# design.net
KiCad netlist of a schematic drawn in Altium Designer
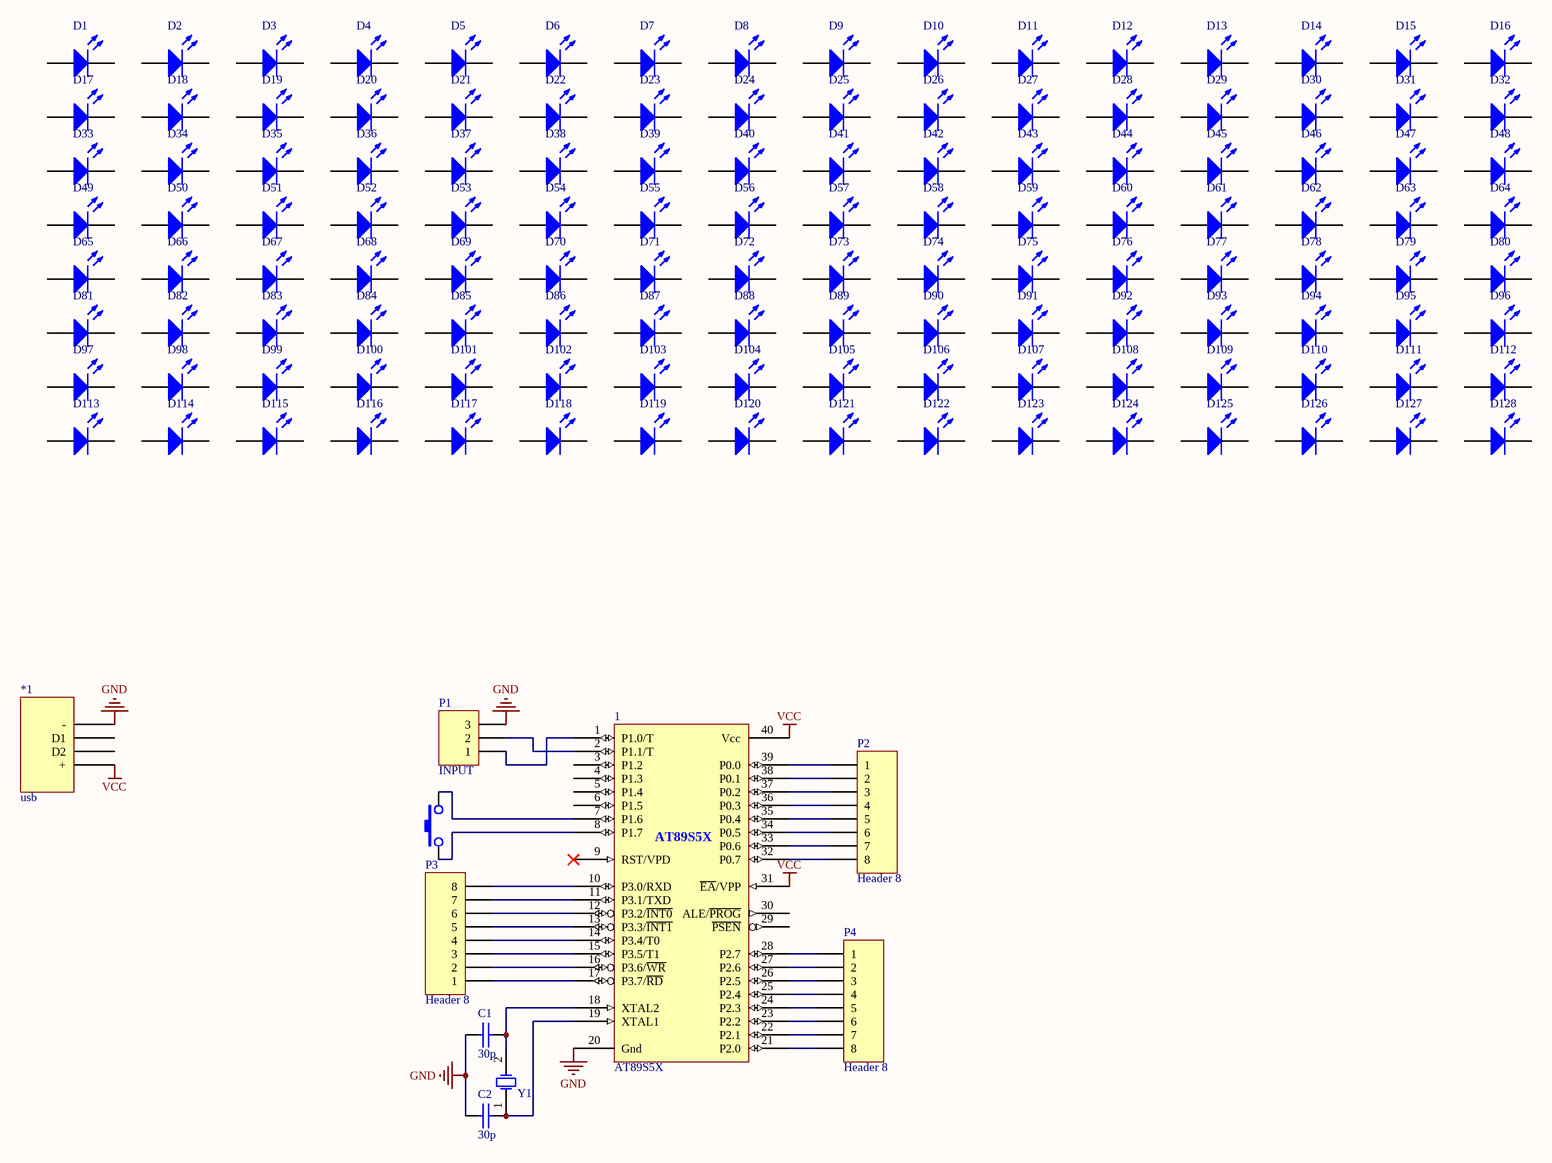
[diagram p0: 单片机频谱显示.SchDoc]

(export (version "E")
  (design (tool "Eeschema 10.0.6"))
  (components
    (comp (ref "*1") (value "usb") (footprint "USB") (libsource (lib "插件") (part "usb")))
    (comp (ref "1") (value "AT89S5X") (footprint "DIP-40") (libsource (lib "单片机及相关") (part "AT89S5X")))
    (comp (ref "C1")
      (value "30p")
      (footprint "RAD0.2")
      (fields (field (name "Comment") "CAP"))
      (libsource (lib "常用元件库") (part "CAP"))
    )
    (comp (ref "C2")
      (value "30p")
      (footprint "RAD0.2")
      (fields (field (name "Comment") "CAP"))
      (libsource (lib "常用元件库") (part "CAP"))
    )
    (comp (ref "D1")
      (value "LED0")
      (footprint "LED")
      (description "Typical INFRARED GaAs LED")
      (fields (field (name "PUBLISHER") "Altium Limited"))
      (libsource (lib "常用元件库") (part "LED0"))
    )
    (comp (ref "D2")
      (value "LED0")
      (footprint "LED")
      (description "Typical INFRARED GaAs LED")
      (fields (field (name "PUBLISHER") "Altium Limited"))
      (libsource (lib "常用元件库") (part "LED0"))
    )
    (comp (ref "D3")
      (value "LED0")
      (footprint "LED")
      (description "Typical INFRARED GaAs LED")
      (fields (field (name "PUBLISHER") "Altium Limited"))
      (libsource (lib "常用元件库") (part "LED0"))
    )
    (comp (ref "D4")
      (value "LED0")
      (footprint "LED")
      (description "Typical INFRARED GaAs LED")
      (fields (field (name "PUBLISHER") "Altium Limited"))
      (libsource (lib "常用元件库") (part "LED0"))
    )
    (comp (ref "D5")
      (value "LED0")
      (footprint "LED")
      (description "Typical INFRARED GaAs LED")
      (fields (field (name "PUBLISHER") "Altium Limited"))
      (libsource (lib "常用元件库") (part "LED0"))
    )
    (comp (ref "D6")
      (value "LED0")
      (footprint "LED")
      (description "Typical INFRARED GaAs LED")
      (fields (field (name "PUBLISHER") "Altium Limited"))
      (libsource (lib "常用元件库") (part "LED0"))
    )
    (comp (ref "D7")
      (value "LED0")
      (footprint "LED")
      (description "Typical INFRARED GaAs LED")
      (fields (field (name "PUBLISHER") "Altium Limited"))
      (libsource (lib "常用元件库") (part "LED0"))
    )
    (comp (ref "D8")
      (value "LED0")
      (footprint "LED")
      (description "Typical INFRARED GaAs LED")
      (fields (field (name "PUBLISHER") "Altium Limited"))
      (libsource (lib "常用元件库") (part "LED0"))
    )
    (comp (ref "D9")
      (value "LED0")
      (footprint "LED")
      (description "Typical INFRARED GaAs LED")
      (fields (field (name "PUBLISHER") "Altium Limited"))
      (libsource (lib "常用元件库") (part "LED0"))
    )
    (comp (ref "D10")
      (value "LED0")
      (footprint "LED")
      (description "Typical INFRARED GaAs LED")
      (fields (field (name "PUBLISHER") "Altium Limited"))
      (libsource (lib "常用元件库") (part "LED0"))
    )
    (comp (ref "D11")
      (value "LED0")
      (footprint "LED")
      (description "Typical INFRARED GaAs LED")
      (fields (field (name "PUBLISHER") "Altium Limited"))
      (libsource (lib "常用元件库") (part "LED0"))
    )
    (comp (ref "D12")
      (value "LED0")
      (footprint "LED")
      (description "Typical INFRARED GaAs LED")
      (fields (field (name "PUBLISHER") "Altium Limited"))
      (libsource (lib "常用元件库") (part "LED0"))
    )
    (comp (ref "D13")
      (value "LED0")
      (footprint "LED")
      (description "Typical INFRARED GaAs LED")
      (fields (field (name "PUBLISHER") "Altium Limited"))
      (libsource (lib "常用元件库") (part "LED0"))
    )
    (comp (ref "D14")
      (value "LED0")
      (footprint "LED")
      (description "Typical INFRARED GaAs LED")
      (fields (field (name "PUBLISHER") "Altium Limited"))
      (libsource (lib "常用元件库") (part "LED0"))
    )
    (comp (ref "D15")
      (value "LED0")
      (footprint "LED")
      (description "Typical INFRARED GaAs LED")
      (fields (field (name "PUBLISHER") "Altium Limited"))
      (libsource (lib "常用元件库") (part "LED0"))
    )
    (comp (ref "D16")
      (value "LED0")
      (footprint "LED")
      (description "Typical INFRARED GaAs LED")
      (fields (field (name "PUBLISHER") "Altium Limited"))
      (libsource (lib "常用元件库") (part "LED0"))
    )
    (comp (ref "D17")
      (value "LED0")
      (footprint "LED")
      (description "Typical INFRARED GaAs LED")
      (fields (field (name "PUBLISHER") "Altium Limited"))
      (libsource (lib "常用元件库") (part "LED0"))
    )
    (comp (ref "D18")
      (value "LED0")
      (footprint "LED")
      (description "Typical INFRARED GaAs LED")
      (fields (field (name "PUBLISHER") "Altium Limited"))
      (libsource (lib "常用元件库") (part "LED0"))
    )
    (comp (ref "D19")
      (value "LED0")
      (footprint "LED")
      (description "Typical INFRARED GaAs LED")
      (fields (field (name "PUBLISHER") "Altium Limited"))
      (libsource (lib "常用元件库") (part "LED0"))
    )
    (comp (ref "D20")
      (value "LED0")
      (footprint "LED")
      (description "Typical INFRARED GaAs LED")
      (fields (field (name "PUBLISHER") "Altium Limited"))
      (libsource (lib "常用元件库") (part "LED0"))
    )
    (comp (ref "D21")
      (value "LED0")
      (footprint "LED")
      (description "Typical INFRARED GaAs LED")
      (fields (field (name "PUBLISHER") "Altium Limited"))
      (libsource (lib "常用元件库") (part "LED0"))
    )
    (comp (ref "D22")
      (value "LED0")
      (footprint "LED")
      (description "Typical INFRARED GaAs LED")
      (fields (field (name "PUBLISHER") "Altium Limited"))
      (libsource (lib "常用元件库") (part "LED0"))
    )
    (comp (ref "D23")
      (value "LED0")
      (footprint "LED")
      (description "Typical INFRARED GaAs LED")
      (fields (field (name "PUBLISHER") "Altium Limited"))
      (libsource (lib "常用元件库") (part "LED0"))
    )
    (comp (ref "D24")
      (value "LED0")
      (footprint "LED")
      (description "Typical INFRARED GaAs LED")
      (fields (field (name "PUBLISHER") "Altium Limited"))
      (libsource (lib "常用元件库") (part "LED0"))
    )
    (comp (ref "D25")
      (value "LED0")
      (footprint "LED")
      (description "Typical INFRARED GaAs LED")
      (fields (field (name "PUBLISHER") "Altium Limited"))
      (libsource (lib "常用元件库") (part "LED0"))
    )
    (comp (ref "D26")
      (value "LED0")
      (footprint "LED")
      (description "Typical INFRARED GaAs LED")
      (fields (field (name "PUBLISHER") "Altium Limited"))
      (libsource (lib "常用元件库") (part "LED0"))
    )
    (comp (ref "D27")
      (value "LED0")
      (footprint "LED")
      (description "Typical INFRARED GaAs LED")
      (fields (field (name "PUBLISHER") "Altium Limited"))
      (libsource (lib "常用元件库") (part "LED0"))
    )
    (comp (ref "D28")
      (value "LED0")
      (footprint "LED")
      (description "Typical INFRARED GaAs LED")
      (fields (field (name "PUBLISHER") "Altium Limited"))
      (libsource (lib "常用元件库") (part "LED0"))
    )
    (comp (ref "D29")
      (value "LED0")
      (footprint "LED")
      (description "Typical INFRARED GaAs LED")
      (fields (field (name "PUBLISHER") "Altium Limited"))
      (libsource (lib "常用元件库") (part "LED0"))
    )
    (comp (ref "D30")
      (value "LED0")
      (footprint "LED")
      (description "Typical INFRARED GaAs LED")
      (fields (field (name "PUBLISHER") "Altium Limited"))
      (libsource (lib "常用元件库") (part "LED0"))
    )
    (comp (ref "D31")
      (value "LED0")
      (footprint "LED")
      (description "Typical INFRARED GaAs LED")
      (fields (field (name "PUBLISHER") "Altium Limited"))
      (libsource (lib "常用元件库") (part "LED0"))
    )
    (comp (ref "D32")
      (value "LED0")
      (footprint "LED")
      (description "Typical INFRARED GaAs LED")
      (fields (field (name "PUBLISHER") "Altium Limited"))
      (libsource (lib "常用元件库") (part "LED0"))
    )
    (comp (ref "D33")
      (value "LED0")
      (footprint "LED")
      (description "Typical INFRARED GaAs LED")
      (fields (field (name "PUBLISHER") "Altium Limited"))
      (libsource (lib "常用元件库") (part "LED0"))
    )
    (comp (ref "D34")
      (value "LED0")
      (footprint "LED")
      (description "Typical INFRARED GaAs LED")
      (fields (field (name "PUBLISHER") "Altium Limited"))
      (libsource (lib "常用元件库") (part "LED0"))
    )
    (comp (ref "D35")
      (value "LED0")
      (footprint "LED")
      (description "Typical INFRARED GaAs LED")
      (fields (field (name "PUBLISHER") "Altium Limited"))
      (libsource (lib "常用元件库") (part "LED0"))
    )
    (comp (ref "D36")
      (value "LED0")
      (footprint "LED")
      (description "Typical INFRARED GaAs LED")
      (fields (field (name "PUBLISHER") "Altium Limited"))
      (libsource (lib "常用元件库") (part "LED0"))
    )
    (comp (ref "D37")
      (value "LED0")
      (footprint "LED")
      (description "Typical INFRARED GaAs LED")
      (fields (field (name "PUBLISHER") "Altium Limited"))
      (libsource (lib "常用元件库") (part "LED0"))
    )
    (comp (ref "D38")
      (value "LED0")
      (footprint "LED")
      (description "Typical INFRARED GaAs LED")
      (fields (field (name "PUBLISHER") "Altium Limited"))
      (libsource (lib "常用元件库") (part "LED0"))
    )
    (comp (ref "D39")
      (value "LED0")
      (footprint "LED")
      (description "Typical INFRARED GaAs LED")
      (fields (field (name "PUBLISHER") "Altium Limited"))
      (libsource (lib "常用元件库") (part "LED0"))
    )
    (comp (ref "D40")
      (value "LED0")
      (footprint "LED")
      (description "Typical INFRARED GaAs LED")
      (fields (field (name "PUBLISHER") "Altium Limited"))
      (libsource (lib "常用元件库") (part "LED0"))
    )
    (comp (ref "D41")
      (value "LED0")
      (footprint "LED")
      (description "Typical INFRARED GaAs LED")
      (fields (field (name "PUBLISHER") "Altium Limited"))
      (libsource (lib "常用元件库") (part "LED0"))
    )
    (comp (ref "D42")
      (value "LED0")
      (footprint "LED")
      (description "Typical INFRARED GaAs LED")
      (fields (field (name "PUBLISHER") "Altium Limited"))
      (libsource (lib "常用元件库") (part "LED0"))
    )
    (comp (ref "D43")
      (value "LED0")
      (footprint "LED")
      (description "Typical INFRARED GaAs LED")
      (fields (field (name "PUBLISHER") "Altium Limited"))
      (libsource (lib "常用元件库") (part "LED0"))
    )
    (comp (ref "D44")
      (value "LED0")
      (footprint "LED")
      (description "Typical INFRARED GaAs LED")
      (fields (field (name "PUBLISHER") "Altium Limited"))
      (libsource (lib "常用元件库") (part "LED0"))
    )
    (comp (ref "D45")
      (value "LED0")
      (footprint "LED")
      (description "Typical INFRARED GaAs LED")
      (fields (field (name "PUBLISHER") "Altium Limited"))
      (libsource (lib "常用元件库") (part "LED0"))
    )
    (comp (ref "D46")
      (value "LED0")
      (footprint "LED")
      (description "Typical INFRARED GaAs LED")
      (fields (field (name "PUBLISHER") "Altium Limited"))
      (libsource (lib "常用元件库") (part "LED0"))
    )
    (comp (ref "D47")
      (value "LED0")
      (footprint "LED")
      (description "Typical INFRARED GaAs LED")
      (fields (field (name "PUBLISHER") "Altium Limited"))
      (libsource (lib "常用元件库") (part "LED0"))
    )
    (comp (ref "D48")
      (value "LED0")
      (footprint "LED")
      (description "Typical INFRARED GaAs LED")
      (fields (field (name "PUBLISHER") "Altium Limited"))
      (libsource (lib "常用元件库") (part "LED0"))
    )
    (comp (ref "D49")
      (value "LED0")
      (footprint "LED")
      (description "Typical INFRARED GaAs LED")
      (fields (field (name "PUBLISHER") "Altium Limited"))
      (libsource (lib "常用元件库") (part "LED0"))
    )
    (comp (ref "D50")
      (value "LED0")
      (footprint "LED")
      (description "Typical INFRARED GaAs LED")
      (fields (field (name "PUBLISHER") "Altium Limited"))
      (libsource (lib "常用元件库") (part "LED0"))
    )
    (comp (ref "D51")
      (value "LED0")
      (footprint "LED")
      (description "Typical INFRARED GaAs LED")
      (fields (field (name "PUBLISHER") "Altium Limited"))
      (libsource (lib "常用元件库") (part "LED0"))
    )
    (comp (ref "D52")
      (value "LED0")
      (footprint "LED")
      (description "Typical INFRARED GaAs LED")
      (fields (field (name "PUBLISHER") "Altium Limited"))
      (libsource (lib "常用元件库") (part "LED0"))
    )
    (comp (ref "D53")
      (value "LED0")
      (footprint "LED")
      (description "Typical INFRARED GaAs LED")
      (fields (field (name "PUBLISHER") "Altium Limited"))
      (libsource (lib "常用元件库") (part "LED0"))
    )
    (comp (ref "D54")
      (value "LED0")
      (footprint "LED")
      (description "Typical INFRARED GaAs LED")
      (fields (field (name "PUBLISHER") "Altium Limited"))
      (libsource (lib "常用元件库") (part "LED0"))
    )
    (comp (ref "D55")
      (value "LED0")
      (footprint "LED")
      (description "Typical INFRARED GaAs LED")
      (fields (field (name "PUBLISHER") "Altium Limited"))
      (libsource (lib "常用元件库") (part "LED0"))
    )
    (comp (ref "D56")
      (value "LED0")
      (footprint "LED")
      (description "Typical INFRARED GaAs LED")
      (fields (field (name "PUBLISHER") "Altium Limited"))
      (libsource (lib "常用元件库") (part "LED0"))
    )
    (comp (ref "D57")
      (value "LED0")
      (footprint "LED")
      (description "Typical INFRARED GaAs LED")
      (fields (field (name "PUBLISHER") "Altium Limited"))
      (libsource (lib "常用元件库") (part "LED0"))
    )
    (comp (ref "D58")
      (value "LED0")
      (footprint "LED")
      (description "Typical INFRARED GaAs LED")
      (fields (field (name "PUBLISHER") "Altium Limited"))
      (libsource (lib "常用元件库") (part "LED0"))
    )
    (comp (ref "D59")
      (value "LED0")
      (footprint "LED")
      (description "Typical INFRARED GaAs LED")
      (fields (field (name "PUBLISHER") "Altium Limited"))
      (libsource (lib "常用元件库") (part "LED0"))
    )
    (comp (ref "D60")
      (value "LED0")
      (footprint "LED")
      (description "Typical INFRARED GaAs LED")
      (fields (field (name "PUBLISHER") "Altium Limited"))
      (libsource (lib "常用元件库") (part "LED0"))
    )
    (comp (ref "D61")
      (value "LED0")
      (footprint "LED")
      (description "Typical INFRARED GaAs LED")
      (fields (field (name "PUBLISHER") "Altium Limited"))
      (libsource (lib "常用元件库") (part "LED0"))
    )
    (comp (ref "D62")
      (value "LED0")
      (footprint "LED")
      (description "Typical INFRARED GaAs LED")
      (fields (field (name "PUBLISHER") "Altium Limited"))
      (libsource (lib "常用元件库") (part "LED0"))
    )
    (comp (ref "D63")
      (value "LED0")
      (footprint "LED")
      (description "Typical INFRARED GaAs LED")
      (fields (field (name "PUBLISHER") "Altium Limited"))
      (libsource (lib "常用元件库") (part "LED0"))
    )
    (comp (ref "D64")
      (value "LED0")
      (footprint "LED")
      (description "Typical INFRARED GaAs LED")
      (fields (field (name "PUBLISHER") "Altium Limited"))
      (libsource (lib "常用元件库") (part "LED0"))
    )
    (comp (ref "D65")
      (value "LED0")
      (footprint "LED")
      (description "Typical INFRARED GaAs LED")
      (fields (field (name "PUBLISHER") "Altium Limited"))
      (libsource (lib "常用元件库") (part "LED0"))
    )
    (comp (ref "D66")
      (value "LED0")
      (footprint "LED")
      (description "Typical INFRARED GaAs LED")
      (fields (field (name "PUBLISHER") "Altium Limited"))
      (libsource (lib "常用元件库") (part "LED0"))
    )
    (comp (ref "D67")
      (value "LED0")
      (footprint "LED")
      (description "Typical INFRARED GaAs LED")
      (fields (field (name "PUBLISHER") "Altium Limited"))
      (libsource (lib "常用元件库") (part "LED0"))
    )
    (comp (ref "D68")
      (value "LED0")
      (footprint "LED")
      (description "Typical INFRARED GaAs LED")
      (fields (field (name "PUBLISHER") "Altium Limited"))
      (libsource (lib "常用元件库") (part "LED0"))
    )
    (comp (ref "D69")
      (value "LED0")
      (footprint "LED")
      (description "Typical INFRARED GaAs LED")
      (fields (field (name "PUBLISHER") "Altium Limited"))
      (libsource (lib "常用元件库") (part "LED0"))
    )
    (comp (ref "D70")
      (value "LED0")
      (footprint "LED")
      (description "Typical INFRARED GaAs LED")
      (fields (field (name "PUBLISHER") "Altium Limited"))
      (libsource (lib "常用元件库") (part "LED0"))
    )
    (comp (ref "D71")
      (value "LED0")
      (footprint "LED")
      (description "Typical INFRARED GaAs LED")
      (fields (field (name "PUBLISHER") "Altium Limited"))
      (libsource (lib "常用元件库") (part "LED0"))
    )
    (comp (ref "D72")
      (value "LED0")
      (footprint "LED")
      (description "Typical INFRARED GaAs LED")
      (fields (field (name "PUBLISHER") "Altium Limited"))
      (libsource (lib "常用元件库") (part "LED0"))
    )
    (comp (ref "D73")
      (value "LED0")
      (footprint "LED")
      (description "Typical INFRARED GaAs LED")
      (fields (field (name "PUBLISHER") "Altium Limited"))
      (libsource (lib "常用元件库") (part "LED0"))
    )
    (comp (ref "D74")
      (value "LED0")
      (footprint "LED")
      (description "Typical INFRARED GaAs LED")
      (fields (field (name "PUBLISHER") "Altium Limited"))
      (libsource (lib "常用元件库") (part "LED0"))
    )
    (comp (ref "D75")
      (value "LED0")
      (footprint "LED")
      (description "Typical INFRARED GaAs LED")
      (fields (field (name "PUBLISHER") "Altium Limited"))
      (libsource (lib "常用元件库") (part "LED0"))
    )
    (comp (ref "D76")
      (value "LED0")
      (footprint "LED")
      (description "Typical INFRARED GaAs LED")
      (fields (field (name "PUBLISHER") "Altium Limited"))
      (libsource (lib "常用元件库") (part "LED0"))
    )
    (comp (ref "D77")
      (value "LED0")
      (footprint "LED")
      (description "Typical INFRARED GaAs LED")
      (fields (field (name "PUBLISHER") "Altium Limited"))
      (libsource (lib "常用元件库") (part "LED0"))
    )
    (comp (ref "D78")
      (value "LED0")
      (footprint "LED")
      (description "Typical INFRARED GaAs LED")
      (fields (field (name "PUBLISHER") "Altium Limited"))
      (libsource (lib "常用元件库") (part "LED0"))
    )
    (comp (ref "D79")
      (value "LED0")
      (footprint "LED")
      (description "Typical INFRARED GaAs LED")
      (fields (field (name "PUBLISHER") "Altium Limited"))
      (libsource (lib "常用元件库") (part "LED0"))
    )
    (comp (ref "D80")
      (value "LED0")
      (footprint "LED")
      (description "Typical INFRARED GaAs LED")
      (fields (field (name "PUBLISHER") "Altium Limited"))
      (libsource (lib "常用元件库") (part "LED0"))
    )
    (comp (ref "D81")
      (value "LED0")
      (footprint "LED")
      (description "Typical INFRARED GaAs LED")
      (fields (field (name "PUBLISHER") "Altium Limited"))
      (libsource (lib "常用元件库") (part "LED0"))
    )
    (comp (ref "D82")
      (value "LED0")
      (footprint "LED")
      (description "Typical INFRARED GaAs LED")
      (fields (field (name "PUBLISHER") "Altium Limited"))
      (libsource (lib "常用元件库") (part "LED0"))
    )
    (comp (ref "D83")
      (value "LED0")
      (footprint "LED")
      (description "Typical INFRARED GaAs LED")
      (fields (field (name "PUBLISHER") "Altium Limited"))
      (libsource (lib "常用元件库") (part "LED0"))
    )
    (comp (ref "D84")
      (value "LED0")
      (footprint "LED")
      (description "Typical INFRARED GaAs LED")
      (fields (field (name "PUBLISHER") "Altium Limited"))
      (libsource (lib "常用元件库") (part "LED0"))
    )
    (comp (ref "D85")
      (value "LED0")
      (footprint "LED")
      (description "Typical INFRARED GaAs LED")
      (fields (field (name "PUBLISHER") "Altium Limited"))
      (libsource (lib "常用元件库") (part "LED0"))
    )
    (comp (ref "D86")
      (value "LED0")
      (footprint "LED")
      (description "Typical INFRARED GaAs LED")
      (fields (field (name "PUBLISHER") "Altium Limited"))
      (libsource (lib "常用元件库") (part "LED0"))
    )
    (comp (ref "D87")
      (value "LED0")
      (footprint "LED")
      (description "Typical INFRARED GaAs LED")
      (fields (field (name "PUBLISHER") "Altium Limited"))
      (libsource (lib "常用元件库") (part "LED0"))
    )
    (comp (ref "D88")
      (value "LED0")
      (footprint "LED")
      (description "Typical INFRARED GaAs LED")
      (fields (field (name "PUBLISHER") "Altium Limited"))
      (libsource (lib "常用元件库") (part "LED0"))
    )
    (comp (ref "D89")
      (value "LED0")
      (footprint "LED")
      (description "Typical INFRARED GaAs LED")
      (fields (field (name "PUBLISHER") "Altium Limited"))
      (libsource (lib "常用元件库") (part "LED0"))
    )
    (comp (ref "D90")
      (value "LED0")
      (footprint "LED")
      (description "Typical INFRARED GaAs LED")
      (fields (field (name "PUBLISHER") "Altium Limited"))
      (libsource (lib "常用元件库") (part "LED0"))
    )
    (comp (ref "D91")
      (value "LED0")
      (footprint "LED")
      (description "Typical INFRARED GaAs LED")
      (fields (field (name "PUBLISHER") "Altium Limited"))
      (libsource (lib "常用元件库") (part "LED0"))
    )
    (comp (ref "D92")
      (value "LED0")
      (footprint "LED")
      (description "Typical INFRARED GaAs LED")
      (fields (field (name "PUBLISHER") "Altium Limited"))
      (libsource (lib "常用元件库") (part "LED0"))
    )
    (comp (ref "D93")
      (value "LED0")
      (footprint "LED")
      (description "Typical INFRARED GaAs LED")
      (fields (field (name "PUBLISHER") "Altium Limited"))
      (libsource (lib "常用元件库") (part "LED0"))
    )
    (comp (ref "D94")
      (value "LED0")
      (footprint "LED")
      (description "Typical INFRARED GaAs LED")
      (fields (field (name "PUBLISHER") "Altium Limited"))
      (libsource (lib "常用元件库") (part "LED0"))
    )
    (comp (ref "D95")
      (value "LED0")
      (footprint "LED")
      (description "Typical INFRARED GaAs LED")
      (fields (field (name "PUBLISHER") "Altium Limited"))
      (libsource (lib "常用元件库") (part "LED0"))
    )
    (comp (ref "D96")
      (value "LED0")
      (footprint "LED")
      (description "Typical INFRARED GaAs LED")
      (fields (field (name "PUBLISHER") "Altium Limited"))
      (libsource (lib "常用元件库") (part "LED0"))
    )
    (comp (ref "D97")
      (value "LED0")
      (footprint "LED")
      (description "Typical INFRARED GaAs LED")
      (fields (field (name "PUBLISHER") "Altium Limited"))
      (libsource (lib "常用元件库") (part "LED0"))
    )
    (comp (ref "D98")
      (value "LED0")
      (footprint "LED")
      (description "Typical INFRARED GaAs LED")
      (fields (field (name "PUBLISHER") "Altium Limited"))
      (libsource (lib "常用元件库") (part "LED0"))
    )
    (comp (ref "D99")
      (value "LED0")
      (footprint "LED")
      (description "Typical INFRARED GaAs LED")
      (fields (field (name "PUBLISHER") "Altium Limited"))
      (libsource (lib "常用元件库") (part "LED0"))
    )
    (comp (ref "D100")
      (value "LED0")
      (footprint "LED")
      (description "Typical INFRARED GaAs LED")
      (fields (field (name "PUBLISHER") "Altium Limited"))
      (libsource (lib "常用元件库") (part "LED0"))
    )
    (comp (ref "D101")
      (value "LED0")
      (footprint "LED")
      (description "Typical INFRARED GaAs LED")
      (fields (field (name "PUBLISHER") "Altium Limited"))
      (libsource (lib "常用元件库") (part "LED0"))
    )
    (comp (ref "D102")
      (value "LED0")
      (footprint "LED")
      (description "Typical INFRARED GaAs LED")
      (fields (field (name "PUBLISHER") "Altium Limited"))
      (libsource (lib "常用元件库") (part "LED0"))
    )
    (comp (ref "D103")
      (value "LED0")
      (footprint "LED")
      (description "Typical INFRARED GaAs LED")
      (fields (field (name "PUBLISHER") "Altium Limited"))
      (libsource (lib "常用元件库") (part "LED0"))
    )
    (comp (ref "D104")
      (value "LED0")
      (footprint "LED")
      (description "Typical INFRARED GaAs LED")
      (fields (field (name "PUBLISHER") "Altium Limited"))
      (libsource (lib "常用元件库") (part "LED0"))
    )
    (comp (ref "D105")
      (value "LED0")
      (footprint "LED")
      (description "Typical INFRARED GaAs LED")
      (fields (field (name "PUBLISHER") "Altium Limited"))
      (libsource (lib "常用元件库") (part "LED0"))
    )
    (comp (ref "D106")
      (value "LED0")
      (footprint "LED")
      (description "Typical INFRARED GaAs LED")
      (fields (field (name "PUBLISHER") "Altium Limited"))
      (libsource (lib "常用元件库") (part "LED0"))
    )
    (comp (ref "D107")
      (value "LED0")
      (footprint "LED")
      (description "Typical INFRARED GaAs LED")
      (fields (field (name "PUBLISHER") "Altium Limited"))
      (libsource (lib "常用元件库") (part "LED0"))
    )
    (comp (ref "D108")
      (value "LED0")
      (footprint "LED")
      (description "Typical INFRARED GaAs LED")
      (fields (field (name "PUBLISHER") "Altium Limited"))
      (libsource (lib "常用元件库") (part "LED0"))
    )
    (comp (ref "D109")
      (value "LED0")
      (footprint "LED")
      (description "Typical INFRARED GaAs LED")
      (fields (field (name "PUBLISHER") "Altium Limited"))
      (libsource (lib "常用元件库") (part "LED0"))
    )
    (comp (ref "D110")
      (value "LED0")
      (footprint "LED")
      (description "Typical INFRARED GaAs LED")
      (fields (field (name "PUBLISHER") "Altium Limited"))
      (libsource (lib "常用元件库") (part "LED0"))
    )
    (comp (ref "D111")
      (value "LED0")
      (footprint "LED")
      (description "Typical INFRARED GaAs LED")
      (fields (field (name "PUBLISHER") "Altium Limited"))
      (libsource (lib "常用元件库") (part "LED0"))
    )
    (comp (ref "D112")
      (value "LED0")
      (footprint "LED")
      (description "Typical INFRARED GaAs LED")
      (fields (field (name "PUBLISHER") "Altium Limited"))
      (libsource (lib "常用元件库") (part "LED0"))
    )
    (comp (ref "D113")
      (value "LED0")
      (footprint "LED")
      (description "Typical INFRARED GaAs LED")
      (fields (field (name "PUBLISHER") "Altium Limited"))
      (libsource (lib "常用元件库") (part "LED0"))
    )
    (comp (ref "D114")
      (value "LED0")
      (footprint "LED")
      (description "Typical INFRARED GaAs LED")
      (fields (field (name "PUBLISHER") "Altium Limited"))
      (libsource (lib "常用元件库") (part "LED0"))
    )
    (comp (ref "D115")
      (value "LED0")
      (footprint "LED")
      (description "Typical INFRARED GaAs LED")
      (fields (field (name "PUBLISHER") "Altium Limited"))
      (libsource (lib "常用元件库") (part "LED0"))
    )
    (comp (ref "D116")
      (value "LED0")
      (footprint "LED")
      (description "Typical INFRARED GaAs LED")
      (fields (field (name "PUBLISHER") "Altium Limited"))
      (libsource (lib "常用元件库") (part "LED0"))
    )
    (comp (ref "D117")
      (value "LED0")
      (footprint "LED")
      (description "Typical INFRARED GaAs LED")
      (fields (field (name "PUBLISHER") "Altium Limited"))
      (libsource (lib "常用元件库") (part "LED0"))
    )
    (comp (ref "D118")
      (value "LED0")
      (footprint "LED")
      (description "Typical INFRARED GaAs LED")
      (fields (field (name "PUBLISHER") "Altium Limited"))
      (libsource (lib "常用元件库") (part "LED0"))
    )
    (comp (ref "D119")
      (value "LED0")
      (footprint "LED")
      (description "Typical INFRARED GaAs LED")
      (fields (field (name "PUBLISHER") "Altium Limited"))
      (libsource (lib "常用元件库") (part "LED0"))
    )
    (comp (ref "D120")
      (value "LED0")
      (footprint "LED")
      (description "Typical INFRARED GaAs LED")
      (fields (field (name "PUBLISHER") "Altium Limited"))
      (libsource (lib "常用元件库") (part "LED0"))
    )
    (comp (ref "D121")
      (value "LED0")
      (footprint "LED")
      (description "Typical INFRARED GaAs LED")
      (fields (field (name "PUBLISHER") "Altium Limited"))
      (libsource (lib "常用元件库") (part "LED0"))
    )
    (comp (ref "D122")
      (value "LED0")
      (footprint "LED")
      (description "Typical INFRARED GaAs LED")
      (fields (field (name "PUBLISHER") "Altium Limited"))
      (libsource (lib "常用元件库") (part "LED0"))
    )
    (comp (ref "D123")
      (value "LED0")
      (footprint "LED")
      (description "Typical INFRARED GaAs LED")
      (fields (field (name "PUBLISHER") "Altium Limited"))
      (libsource (lib "常用元件库") (part "LED0"))
    )
    (comp (ref "D124")
      (value "LED0")
      (footprint "LED")
      (description "Typical INFRARED GaAs LED")
      (fields (field (name "PUBLISHER") "Altium Limited"))
      (libsource (lib "常用元件库") (part "LED0"))
    )
    (comp (ref "D125")
      (value "LED0")
      (footprint "LED")
      (description "Typical INFRARED GaAs LED")
      (fields (field (name "PUBLISHER") "Altium Limited"))
      (libsource (lib "常用元件库") (part "LED0"))
    )
    (comp (ref "D126")
      (value "LED0")
      (footprint "LED")
      (description "Typical INFRARED GaAs LED")
      (fields (field (name "PUBLISHER") "Altium Limited"))
      (libsource (lib "常用元件库") (part "LED0"))
    )
    (comp (ref "D127")
      (value "LED0")
      (footprint "LED")
      (description "Typical INFRARED GaAs LED")
      (fields (field (name "PUBLISHER") "Altium Limited"))
      (libsource (lib "常用元件库") (part "LED0"))
    )
    (comp (ref "D128")
      (value "LED0")
      (footprint "LED")
      (description "Typical INFRARED GaAs LED")
      (fields (field (name "PUBLISHER") "Altium Limited"))
      (libsource (lib "常用元件库") (part "LED0"))
    )
    (comp (ref "key1") (value "KEY") (footprint "KeyA") (libsource (lib "常用元件库") (part "KEY")))
    (comp (ref "P1")
      (value "INPUT")
      (footprint "HDR1X3")
      (description "Header, 3-Pin")
      (fields (field (name "PUBLISHER") "Altium Limited"))
      (libsource (lib "常用元件库") (part "Header 3"))
    )
    (comp (ref "P2")
      (value "Header 8")
      (footprint "HDR1X8")
      (description "Header, 8-Pin")
      (fields (field (name "PUBLISHER") "Altium Limited"))
      (libsource (lib "") (part "Header 8_1"))
    )
    (comp (ref "P3")
      (value "Header 8")
      (footprint "HDR1X8")
      (description "Header, 8-Pin")
      (fields (field (name "PUBLISHER") "Altium Limited"))
      (libsource (lib "常用元件库") (part "Header 8"))
    )
    (comp (ref "P4")
      (value "Header 8")
      (footprint "HDR1X8")
      (description "Header, 8-Pin")
      (fields (field (name "PUBLISHER") "Altium Limited"))
      (libsource (lib "") (part "Header 8_1"))
    )
    (comp (ref "Y1")
      (value "XTAL")
      (footprint "XTAL")
      (description "Crystal Oscillator")
      (fields (field (name "PUBLISHER") "Altium Limited"))
      (libsource (lib "常用元件库") (part "XTAL"))
    )
  )
  (nets
    (net (code "1") (name "GND") (class "Default")
      (node (ref "*1") (pin "-") (pinfunction "-_-") (pintype "power_in"))
      (node (ref "1") (pin "20") (pinfunction "Gnd_20") (pintype "power_in"))
      (node (ref "C1") (pin "1") (pinfunction "1_1") (pintype "passive"))
      (node (ref "C2") (pin "1") (pinfunction "1_1") (pintype "passive"))
      (node (ref "P1") (pin "3") (pinfunction "3_3") (pintype "passive"))
    )
    (net (code "2") (name "Net-(1-P0.0)") (class "Default")
      (node (ref "1") (pin "39") (pinfunction "P0.0_39") (pintype "bidirectional"))
      (node (ref "P2") (pin "1") (pinfunction "1_1") (pintype "passive"))
    )
    (net (code "3") (name "Net-(1-P0.1)") (class "Default")
      (node (ref "1") (pin "38") (pinfunction "P0.1_38") (pintype "bidirectional"))
      (node (ref "P2") (pin "2") (pinfunction "2_2") (pintype "passive"))
    )
    (net (code "4") (name "Net-(1-P0.2)") (class "Default")
      (node (ref "1") (pin "37") (pinfunction "P0.2_37") (pintype "bidirectional"))
      (node (ref "P2") (pin "3") (pinfunction "3_3") (pintype "passive"))
    )
    (net (code "5") (name "Net-(1-P0.3)") (class "Default")
      (node (ref "1") (pin "36") (pinfunction "P0.3_36") (pintype "bidirectional"))
      (node (ref "P2") (pin "4") (pinfunction "4_4") (pintype "passive"))
    )
    (net (code "6") (name "Net-(1-P0.4)") (class "Default")
      (node (ref "1") (pin "35") (pinfunction "P0.4_35") (pintype "bidirectional"))
      (node (ref "P2") (pin "5") (pinfunction "5_5") (pintype "passive"))
    )
    (net (code "7") (name "Net-(1-P0.5)") (class "Default")
      (node (ref "1") (pin "34") (pinfunction "P0.5_34") (pintype "bidirectional"))
      (node (ref "P2") (pin "6") (pinfunction "6_6") (pintype "passive"))
    )
    (net (code "8") (name "Net-(1-P0.6)") (class "Default")
      (node (ref "1") (pin "33") (pinfunction "P0.6_33") (pintype "bidirectional"))
      (node (ref "P2") (pin "7") (pinfunction "7_7") (pintype "passive"))
    )
    (net (code "9") (name "Net-(1-P0.7)") (class "Default")
      (node (ref "1") (pin "32") (pinfunction "P0.7_32") (pintype "bidirectional"))
      (node (ref "P2") (pin "8") (pinfunction "8_8") (pintype "passive"))
    )
    (net (code "10") (name "Net-(1-P1.0{slash}T)") (class "Default")
      (node (ref "1") (pin "1") (pinfunction "P1.0/T_1") (pintype "bidirectional"))
      (node (ref "P1") (pin "1") (pinfunction "1_1") (pintype "passive"))
    )
    (net (code "11") (name "Net-(1-P1.1{slash}T)") (class "Default")
      (node (ref "1") (pin "2") (pinfunction "P1.1/T_2") (pintype "bidirectional"))
      (node (ref "P1") (pin "2") (pinfunction "2_2") (pintype "passive"))
    )
    (net (code "12") (name "Net-(1-P1.6)") (class "Default")
      (node (ref "1") (pin "7") (pinfunction "P1.6_7") (pintype "bidirectional"))
      (node (ref "key1") (pin "2") (pinfunction "2_2") (pintype "passive"))
    )
    (net (code "13") (name "Net-(1-P1.7)") (class "Default")
      (node (ref "1") (pin "8") (pinfunction "P1.7_8") (pintype "bidirectional"))
      (node (ref "key1") (pin "1") (pinfunction "1_1") (pintype "passive"))
    )
    (net (code "14") (name "Net-(1-P2.0)") (class "Default")
      (node (ref "1") (pin "21") (pinfunction "P2.0_21") (pintype "bidirectional"))
      (node (ref "P4") (pin "8") (pinfunction "8_8") (pintype "passive"))
    )
    (net (code "15") (name "Net-(1-P2.1)") (class "Default")
      (node (ref "1") (pin "22") (pinfunction "P2.1_22") (pintype "bidirectional"))
      (node (ref "P4") (pin "7") (pinfunction "7_7") (pintype "passive"))
    )
    (net (code "16") (name "Net-(1-P2.2)") (class "Default")
      (node (ref "1") (pin "23") (pinfunction "P2.2_23") (pintype "bidirectional"))
      (node (ref "P4") (pin "6") (pinfunction "6_6") (pintype "passive"))
    )
    (net (code "17") (name "Net-(1-P2.3)") (class "Default")
      (node (ref "1") (pin "24") (pinfunction "P2.3_24") (pintype "bidirectional"))
      (node (ref "P4") (pin "5") (pinfunction "5_5") (pintype "passive"))
    )
    (net (code "18") (name "Net-(1-P2.4)") (class "Default")
      (node (ref "1") (pin "25") (pinfunction "P2.4_25") (pintype "bidirectional"))
      (node (ref "P4") (pin "4") (pinfunction "4_4") (pintype "passive"))
    )
    (net (code "19") (name "Net-(1-P2.5)") (class "Default")
      (node (ref "1") (pin "26") (pinfunction "P2.5_26") (pintype "bidirectional"))
      (node (ref "P4") (pin "3") (pinfunction "3_3") (pintype "passive"))
    )
    (net (code "20") (name "Net-(1-P2.6)") (class "Default")
      (node (ref "1") (pin "27") (pinfunction "P2.6_27") (pintype "bidirectional"))
      (node (ref "P4") (pin "2") (pinfunction "2_2") (pintype "passive"))
    )
    (net (code "21") (name "Net-(1-P2.7)") (class "Default")
      (node (ref "1") (pin "28") (pinfunction "P2.7_28") (pintype "bidirectional"))
      (node (ref "P4") (pin "1") (pinfunction "1_1") (pintype "passive"))
    )
    (net (code "22") (name "Net-(1-P3.0{slash}RXD)") (class "Default")
      (node (ref "1") (pin "10") (pinfunction "P3.0/RXD_10") (pintype "bidirectional"))
      (node (ref "P3") (pin "8") (pinfunction "8_8") (pintype "passive"))
    )
    (net (code "23") (name "Net-(1-P3.1{slash}TXD)") (class "Default")
      (node (ref "1") (pin "11") (pinfunction "P3.1/TXD_11") (pintype "bidirectional"))
      (node (ref "P3") (pin "7") (pinfunction "7_7") (pintype "passive"))
    )
    (net (code "24") (name "Net-(1-P3.2{slash}~{INT0})") (class "Default")
      (node (ref "1") (pin "12") (pinfunction "P3.2/~{INT0}_12") (pintype "bidirectional"))
      (node (ref "P3") (pin "6") (pinfunction "6_6") (pintype "passive"))
    )
    (net (code "25") (name "Net-(1-P3.3{slash}~{INT1})") (class "Default")
      (node (ref "1") (pin "13") (pinfunction "P3.3/~{INT1}_13") (pintype "bidirectional"))
      (node (ref "P3") (pin "5") (pinfunction "5_5") (pintype "passive"))
    )
    (net (code "26") (name "Net-(1-P3.4{slash}T0)") (class "Default")
      (node (ref "1") (pin "14") (pinfunction "P3.4/T0_14") (pintype "bidirectional"))
      (node (ref "P3") (pin "4") (pinfunction "4_4") (pintype "passive"))
    )
    (net (code "27") (name "Net-(1-P3.5{slash}T1)") (class "Default")
      (node (ref "1") (pin "15") (pinfunction "P3.5/T1_15") (pintype "bidirectional"))
      (node (ref "P3") (pin "3") (pinfunction "3_3") (pintype "passive"))
    )
    (net (code "28") (name "Net-(1-P3.6{slash}~{WR})") (class "Default")
      (node (ref "1") (pin "16") (pinfunction "P3.6/~{WR}_16") (pintype "bidirectional"))
      (node (ref "P3") (pin "2") (pinfunction "2_2") (pintype "passive"))
    )
    (net (code "29") (name "Net-(1-P3.7{slash}~{RD})") (class "Default")
      (node (ref "1") (pin "17") (pinfunction "P3.7/~{RD}_17") (pintype "bidirectional"))
      (node (ref "P3") (pin "1") (pinfunction "1_1") (pintype "passive"))
    )
    (net (code "30") (name "Net-(1-XTAL1)") (class "Default")
      (node (ref "1") (pin "19") (pinfunction "XTAL1_19") (pintype "input"))
      (node (ref "C2") (pin "2") (pinfunction "2_2") (pintype "passive"))
      (node (ref "Y1") (pin "1") (pinfunction "OSC1_1") (pintype "passive"))
    )
    (net (code "31") (name "Net-(1-XTAL2)") (class "Default")
      (node (ref "1") (pin "18") (pinfunction "XTAL2_18") (pintype "input"))
      (node (ref "C1") (pin "2") (pinfunction "2_2") (pintype "passive"))
      (node (ref "Y1") (pin "2") (pinfunction "OSC2_2") (pintype "passive"))
    )
    (net (code "32") (name "VCC") (class "Default")
      (node (ref "*1") (pin "+") (pinfunction "+_+") (pintype "power_in"))
      (node (ref "1") (pin "31") (pinfunction "~{EA}/VPP_31") (pintype "input"))
      (node (ref "1") (pin "40") (pinfunction "Vcc_40") (pintype "power_in"))
    )
    (net (code "33") (name "unconnected-(*1-PadD1)") (class "Default")
      (node (ref "*1") (pin "D1") (pinfunction "D1_D1") (pintype "passive"))
    )
    (net (code "34") (name "unconnected-(*1-PadD2)") (class "Default")
      (node (ref "*1") (pin "D2") (pinfunction "D2_D2") (pintype "passive"))
    )
    (net (code "35") (name "unconnected-(*1-PadNP)") (class "Default")
      (node (ref "*1") (pin "NP") (pinfunction "NP_NP") (pintype "passive"))
    )
    (net (code "36") (name "unconnected-(*1-PadNP)_1") (class "Default")
      (node (ref "*1") (pin "NP") (pinfunction "NP_NP") (pintype "passive"))
    )
    (net (code "37") (name "unconnected-(1-ALE{slash}~{PROG}-Pad30)") (class "Default")
      (node (ref "1") (pin "30") (pinfunction "ALE/~{PROG}_30") (pintype "output"))
    )
    (net (code "38") (name "unconnected-(1-P1.2-Pad3)") (class "Default")
      (node (ref "1") (pin "3") (pinfunction "P1.2_3") (pintype "bidirectional"))
    )
    (net (code "39") (name "unconnected-(1-P1.3-Pad4)") (class "Default")
      (node (ref "1") (pin "4") (pinfunction "P1.3_4") (pintype "bidirectional"))
    )
    (net (code "40") (name "unconnected-(1-P1.4-Pad5)") (class "Default")
      (node (ref "1") (pin "5") (pinfunction "P1.4_5") (pintype "bidirectional"))
    )
    (net (code "41") (name "unconnected-(1-P1.5-Pad6)") (class "Default")
      (node (ref "1") (pin "6") (pinfunction "P1.5_6") (pintype "bidirectional"))
    )
    (net (code "42") (name "unconnected-(1-RST{slash}VPD-Pad9)") (class "Default")
      (node (ref "1") (pin "9") (pinfunction "RST/VPD_9") (pintype "input+no_connect"))
    )
    (net (code "43") (name "unconnected-(1-~{PSEN}-Pad29)") (class "Default")
      (node (ref "1") (pin "29") (pinfunction "~{PSEN}_29") (pintype "output"))
    )
    (net (code "44") (name "unconnected-(D1-A-Pad1)") (class "Default")
      (node (ref "D1") (pin "1") (pinfunction "A_1") (pintype "passive"))
    )
    (net (code "45") (name "unconnected-(D1-K-Pad2)") (class "Default")
      (node (ref "D1") (pin "2") (pinfunction "K_2") (pintype "passive"))
    )
    (net (code "46") (name "unconnected-(D2-A-Pad1)") (class "Default")
      (node (ref "D2") (pin "1") (pinfunction "A_1") (pintype "passive"))
    )
    (net (code "47") (name "unconnected-(D2-K-Pad2)") (class "Default")
      (node (ref "D2") (pin "2") (pinfunction "K_2") (pintype "passive"))
    )
    (net (code "48") (name "unconnected-(D3-A-Pad1)") (class "Default")
      (node (ref "D3") (pin "1") (pinfunction "A_1") (pintype "passive"))
    )
    (net (code "49") (name "unconnected-(D3-K-Pad2)") (class "Default")
      (node (ref "D3") (pin "2") (pinfunction "K_2") (pintype "passive"))
    )
    (net (code "50") (name "unconnected-(D4-A-Pad1)") (class "Default")
      (node (ref "D4") (pin "1") (pinfunction "A_1") (pintype "passive"))
    )
    (net (code "51") (name "unconnected-(D4-K-Pad2)") (class "Default")
      (node (ref "D4") (pin "2") (pinfunction "K_2") (pintype "passive"))
    )
    (net (code "52") (name "unconnected-(D5-A-Pad1)") (class "Default")
      (node (ref "D5") (pin "1") (pinfunction "A_1") (pintype "passive"))
    )
    (net (code "53") (name "unconnected-(D5-K-Pad2)") (class "Default")
      (node (ref "D5") (pin "2") (pinfunction "K_2") (pintype "passive"))
    )
    (net (code "54") (name "unconnected-(D6-A-Pad1)") (class "Default")
      (node (ref "D6") (pin "1") (pinfunction "A_1") (pintype "passive"))
    )
    (net (code "55") (name "unconnected-(D6-K-Pad2)") (class "Default")
      (node (ref "D6") (pin "2") (pinfunction "K_2") (pintype "passive"))
    )
    (net (code "56") (name "unconnected-(D7-A-Pad1)") (class "Default")
      (node (ref "D7") (pin "1") (pinfunction "A_1") (pintype "passive"))
    )
    (net (code "57") (name "unconnected-(D7-K-Pad2)") (class "Default")
      (node (ref "D7") (pin "2") (pinfunction "K_2") (pintype "passive"))
    )
    (net (code "58") (name "unconnected-(D8-A-Pad1)") (class "Default")
      (node (ref "D8") (pin "1") (pinfunction "A_1") (pintype "passive"))
    )
    (net (code "59") (name "unconnected-(D8-K-Pad2)") (class "Default")
      (node (ref "D8") (pin "2") (pinfunction "K_2") (pintype "passive"))
    )
    (net (code "60") (name "unconnected-(D9-A-Pad1)") (class "Default")
      (node (ref "D9") (pin "1") (pinfunction "A_1") (pintype "passive"))
    )
    (net (code "61") (name "unconnected-(D9-K-Pad2)") (class "Default")
      (node (ref "D9") (pin "2") (pinfunction "K_2") (pintype "passive"))
    )
    (net (code "62") (name "unconnected-(D10-A-Pad1)") (class "Default")
      (node (ref "D10") (pin "1") (pinfunction "A_1") (pintype "passive"))
    )
    (net (code "63") (name "unconnected-(D10-K-Pad2)") (class "Default")
      (node (ref "D10") (pin "2") (pinfunction "K_2") (pintype "passive"))
    )
    (net (code "64") (name "unconnected-(D11-A-Pad1)") (class "Default")
      (node (ref "D11") (pin "1") (pinfunction "A_1") (pintype "passive"))
    )
    (net (code "65") (name "unconnected-(D11-K-Pad2)") (class "Default")
      (node (ref "D11") (pin "2") (pinfunction "K_2") (pintype "passive"))
    )
    (net (code "66") (name "unconnected-(D12-A-Pad1)") (class "Default")
      (node (ref "D12") (pin "1") (pinfunction "A_1") (pintype "passive"))
    )
    (net (code "67") (name "unconnected-(D12-K-Pad2)") (class "Default")
      (node (ref "D12") (pin "2") (pinfunction "K_2") (pintype "passive"))
    )
    (net (code "68") (name "unconnected-(D13-A-Pad1)") (class "Default")
      (node (ref "D13") (pin "1") (pinfunction "A_1") (pintype "passive"))
    )
    (net (code "69") (name "unconnected-(D13-K-Pad2)") (class "Default")
      (node (ref "D13") (pin "2") (pinfunction "K_2") (pintype "passive"))
    )
    (net (code "70") (name "unconnected-(D14-A-Pad1)") (class "Default")
      (node (ref "D14") (pin "1") (pinfunction "A_1") (pintype "passive"))
    )
    (net (code "71") (name "unconnected-(D14-K-Pad2)") (class "Default")
      (node (ref "D14") (pin "2") (pinfunction "K_2") (pintype "passive"))
    )
    (net (code "72") (name "unconnected-(D15-A-Pad1)") (class "Default")
      (node (ref "D15") (pin "1") (pinfunction "A_1") (pintype "passive"))
    )
    (net (code "73") (name "unconnected-(D15-K-Pad2)") (class "Default")
      (node (ref "D15") (pin "2") (pinfunction "K_2") (pintype "passive"))
    )
    (net (code "74") (name "unconnected-(D16-A-Pad1)") (class "Default")
      (node (ref "D16") (pin "1") (pinfunction "A_1") (pintype "passive"))
    )
    (net (code "75") (name "unconnected-(D16-K-Pad2)") (class "Default")
      (node (ref "D16") (pin "2") (pinfunction "K_2") (pintype "passive"))
    )
    (net (code "76") (name "unconnected-(D17-A-Pad1)") (class "Default")
      (node (ref "D17") (pin "1") (pinfunction "A_1") (pintype "passive"))
    )
    (net (code "77") (name "unconnected-(D17-K-Pad2)") (class "Default")
      (node (ref "D17") (pin "2") (pinfunction "K_2") (pintype "passive"))
    )
    (net (code "78") (name "unconnected-(D18-A-Pad1)") (class "Default")
      (node (ref "D18") (pin "1") (pinfunction "A_1") (pintype "passive"))
    )
    (net (code "79") (name "unconnected-(D18-K-Pad2)") (class "Default")
      (node (ref "D18") (pin "2") (pinfunction "K_2") (pintype "passive"))
    )
    (net (code "80") (name "unconnected-(D19-A-Pad1)") (class "Default")
      (node (ref "D19") (pin "1") (pinfunction "A_1") (pintype "passive"))
    )
    (net (code "81") (name "unconnected-(D19-K-Pad2)") (class "Default")
      (node (ref "D19") (pin "2") (pinfunction "K_2") (pintype "passive"))
    )
    (net (code "82") (name "unconnected-(D20-A-Pad1)") (class "Default")
      (node (ref "D20") (pin "1") (pinfunction "A_1") (pintype "passive"))
    )
    (net (code "83") (name "unconnected-(D20-K-Pad2)") (class "Default")
      (node (ref "D20") (pin "2") (pinfunction "K_2") (pintype "passive"))
    )
    (net (code "84") (name "unconnected-(D21-A-Pad1)") (class "Default")
      (node (ref "D21") (pin "1") (pinfunction "A_1") (pintype "passive"))
    )
    (net (code "85") (name "unconnected-(D21-K-Pad2)") (class "Default")
      (node (ref "D21") (pin "2") (pinfunction "K_2") (pintype "passive"))
    )
    (net (code "86") (name "unconnected-(D22-A-Pad1)") (class "Default")
      (node (ref "D22") (pin "1") (pinfunction "A_1") (pintype "passive"))
    )
    (net (code "87") (name "unconnected-(D22-K-Pad2)") (class "Default")
      (node (ref "D22") (pin "2") (pinfunction "K_2") (pintype "passive"))
    )
    (net (code "88") (name "unconnected-(D23-A-Pad1)") (class "Default")
      (node (ref "D23") (pin "1") (pinfunction "A_1") (pintype "passive"))
    )
    (net (code "89") (name "unconnected-(D23-K-Pad2)") (class "Default")
      (node (ref "D23") (pin "2") (pinfunction "K_2") (pintype "passive"))
    )
    (net (code "90") (name "unconnected-(D24-A-Pad1)") (class "Default")
      (node (ref "D24") (pin "1") (pinfunction "A_1") (pintype "passive"))
    )
    (net (code "91") (name "unconnected-(D24-K-Pad2)") (class "Default")
      (node (ref "D24") (pin "2") (pinfunction "K_2") (pintype "passive"))
    )
    (net (code "92") (name "unconnected-(D25-A-Pad1)") (class "Default")
      (node (ref "D25") (pin "1") (pinfunction "A_1") (pintype "passive"))
    )
    (net (code "93") (name "unconnected-(D25-K-Pad2)") (class "Default")
      (node (ref "D25") (pin "2") (pinfunction "K_2") (pintype "passive"))
    )
    (net (code "94") (name "unconnected-(D26-A-Pad1)") (class "Default")
      (node (ref "D26") (pin "1") (pinfunction "A_1") (pintype "passive"))
    )
    (net (code "95") (name "unconnected-(D26-K-Pad2)") (class "Default")
      (node (ref "D26") (pin "2") (pinfunction "K_2") (pintype "passive"))
    )
    (net (code "96") (name "unconnected-(D27-A-Pad1)") (class "Default")
      (node (ref "D27") (pin "1") (pinfunction "A_1") (pintype "passive"))
    )
    (net (code "97") (name "unconnected-(D27-K-Pad2)") (class "Default")
      (node (ref "D27") (pin "2") (pinfunction "K_2") (pintype "passive"))
    )
    (net (code "98") (name "unconnected-(D28-A-Pad1)") (class "Default")
      (node (ref "D28") (pin "1") (pinfunction "A_1") (pintype "passive"))
    )
    (net (code "99") (name "unconnected-(D28-K-Pad2)") (class "Default")
      (node (ref "D28") (pin "2") (pinfunction "K_2") (pintype "passive"))
    )
    (net (code "100") (name "unconnected-(D29-A-Pad1)") (class "Default")
      (node (ref "D29") (pin "1") (pinfunction "A_1") (pintype "passive"))
    )
    (net (code "101") (name "unconnected-(D29-K-Pad2)") (class "Default")
      (node (ref "D29") (pin "2") (pinfunction "K_2") (pintype "passive"))
    )
    (net (code "102") (name "unconnected-(D30-A-Pad1)") (class "Default")
      (node (ref "D30") (pin "1") (pinfunction "A_1") (pintype "passive"))
    )
    (net (code "103") (name "unconnected-(D30-K-Pad2)") (class "Default")
      (node (ref "D30") (pin "2") (pinfunction "K_2") (pintype "passive"))
    )
    (net (code "104") (name "unconnected-(D31-A-Pad1)") (class "Default")
      (node (ref "D31") (pin "1") (pinfunction "A_1") (pintype "passive"))
    )
    (net (code "105") (name "unconnected-(D31-K-Pad2)") (class "Default")
      (node (ref "D31") (pin "2") (pinfunction "K_2") (pintype "passive"))
    )
    (net (code "106") (name "unconnected-(D32-A-Pad1)") (class "Default")
      (node (ref "D32") (pin "1") (pinfunction "A_1") (pintype "passive"))
    )
    (net (code "107") (name "unconnected-(D32-K-Pad2)") (class "Default")
      (node (ref "D32") (pin "2") (pinfunction "K_2") (pintype "passive"))
    )
    (net (code "108") (name "unconnected-(D33-A-Pad1)") (class "Default")
      (node (ref "D33") (pin "1") (pinfunction "A_1") (pintype "passive"))
    )
    (net (code "109") (name "unconnected-(D33-K-Pad2)") (class "Default")
      (node (ref "D33") (pin "2") (pinfunction "K_2") (pintype "passive"))
    )
    (net (code "110") (name "unconnected-(D34-A-Pad1)") (class "Default")
      (node (ref "D34") (pin "1") (pinfunction "A_1") (pintype "passive"))
    )
    (net (code "111") (name "unconnected-(D34-K-Pad2)") (class "Default")
      (node (ref "D34") (pin "2") (pinfunction "K_2") (pintype "passive"))
    )
    (net (code "112") (name "unconnected-(D35-A-Pad1)") (class "Default")
      (node (ref "D35") (pin "1") (pinfunction "A_1") (pintype "passive"))
    )
    (net (code "113") (name "unconnected-(D35-K-Pad2)") (class "Default")
      (node (ref "D35") (pin "2") (pinfunction "K_2") (pintype "passive"))
    )
    (net (code "114") (name "unconnected-(D36-A-Pad1)") (class "Default")
      (node (ref "D36") (pin "1") (pinfunction "A_1") (pintype "passive"))
    )
    (net (code "115") (name "unconnected-(D36-K-Pad2)") (class "Default")
      (node (ref "D36") (pin "2") (pinfunction "K_2") (pintype "passive"))
    )
    (net (code "116") (name "unconnected-(D37-A-Pad1)") (class "Default")
      (node (ref "D37") (pin "1") (pinfunction "A_1") (pintype "passive"))
    )
    (net (code "117") (name "unconnected-(D37-K-Pad2)") (class "Default")
      (node (ref "D37") (pin "2") (pinfunction "K_2") (pintype "passive"))
    )
    (net (code "118") (name "unconnected-(D38-A-Pad1)") (class "Default")
      (node (ref "D38") (pin "1") (pinfunction "A_1") (pintype "passive"))
    )
    (net (code "119") (name "unconnected-(D38-K-Pad2)") (class "Default")
      (node (ref "D38") (pin "2") (pinfunction "K_2") (pintype "passive"))
    )
    (net (code "120") (name "unconnected-(D39-A-Pad1)") (class "Default")
      (node (ref "D39") (pin "1") (pinfunction "A_1") (pintype "passive"))
    )
    (net (code "121") (name "unconnected-(D39-K-Pad2)") (class "Default")
      (node (ref "D39") (pin "2") (pinfunction "K_2") (pintype "passive"))
    )
    (net (code "122") (name "unconnected-(D40-A-Pad1)") (class "Default")
      (node (ref "D40") (pin "1") (pinfunction "A_1") (pintype "passive"))
    )
    (net (code "123") (name "unconnected-(D40-K-Pad2)") (class "Default")
      (node (ref "D40") (pin "2") (pinfunction "K_2") (pintype "passive"))
    )
    (net (code "124") (name "unconnected-(D41-A-Pad1)") (class "Default")
      (node (ref "D41") (pin "1") (pinfunction "A_1") (pintype "passive"))
    )
    (net (code "125") (name "unconnected-(D41-K-Pad2)") (class "Default")
      (node (ref "D41") (pin "2") (pinfunction "K_2") (pintype "passive"))
    )
    (net (code "126") (name "unconnected-(D42-A-Pad1)") (class "Default")
      (node (ref "D42") (pin "1") (pinfunction "A_1") (pintype "passive"))
    )
    (net (code "127") (name "unconnected-(D42-K-Pad2)") (class "Default")
      (node (ref "D42") (pin "2") (pinfunction "K_2") (pintype "passive"))
    )
    (net (code "128") (name "unconnected-(D43-A-Pad1)") (class "Default")
      (node (ref "D43") (pin "1") (pinfunction "A_1") (pintype "passive"))
    )
    (net (code "129") (name "unconnected-(D43-K-Pad2)") (class "Default")
      (node (ref "D43") (pin "2") (pinfunction "K_2") (pintype "passive"))
    )
    (net (code "130") (name "unconnected-(D44-A-Pad1)") (class "Default")
      (node (ref "D44") (pin "1") (pinfunction "A_1") (pintype "passive"))
    )
    (net (code "131") (name "unconnected-(D44-K-Pad2)") (class "Default")
      (node (ref "D44") (pin "2") (pinfunction "K_2") (pintype "passive"))
    )
    (net (code "132") (name "unconnected-(D45-A-Pad1)") (class "Default")
      (node (ref "D45") (pin "1") (pinfunction "A_1") (pintype "passive"))
    )
    (net (code "133") (name "unconnected-(D45-K-Pad2)") (class "Default")
      (node (ref "D45") (pin "2") (pinfunction "K_2") (pintype "passive"))
    )
    (net (code "134") (name "unconnected-(D46-A-Pad1)") (class "Default")
      (node (ref "D46") (pin "1") (pinfunction "A_1") (pintype "passive"))
    )
    (net (code "135") (name "unconnected-(D46-K-Pad2)") (class "Default")
      (node (ref "D46") (pin "2") (pinfunction "K_2") (pintype "passive"))
    )
    (net (code "136") (name "unconnected-(D47-A-Pad1)") (class "Default")
      (node (ref "D47") (pin "1") (pinfunction "A_1") (pintype "passive"))
    )
    (net (code "137") (name "unconnected-(D47-K-Pad2)") (class "Default")
      (node (ref "D47") (pin "2") (pinfunction "K_2") (pintype "passive"))
    )
    (net (code "138") (name "unconnected-(D48-A-Pad1)") (class "Default")
      (node (ref "D48") (pin "1") (pinfunction "A_1") (pintype "passive"))
    )
    (net (code "139") (name "unconnected-(D48-K-Pad2)") (class "Default")
      (node (ref "D48") (pin "2") (pinfunction "K_2") (pintype "passive"))
    )
    (net (code "140") (name "unconnected-(D49-A-Pad1)") (class "Default")
      (node (ref "D49") (pin "1") (pinfunction "A_1") (pintype "passive"))
    )
    (net (code "141") (name "unconnected-(D49-K-Pad2)") (class "Default")
      (node (ref "D49") (pin "2") (pinfunction "K_2") (pintype "passive"))
    )
    (net (code "142") (name "unconnected-(D50-A-Pad1)") (class "Default")
      (node (ref "D50") (pin "1") (pinfunction "A_1") (pintype "passive"))
    )
    (net (code "143") (name "unconnected-(D50-K-Pad2)") (class "Default")
      (node (ref "D50") (pin "2") (pinfunction "K_2") (pintype "passive"))
    )
    (net (code "144") (name "unconnected-(D51-A-Pad1)") (class "Default")
      (node (ref "D51") (pin "1") (pinfunction "A_1") (pintype "passive"))
    )
    (net (code "145") (name "unconnected-(D51-K-Pad2)") (class "Default")
      (node (ref "D51") (pin "2") (pinfunction "K_2") (pintype "passive"))
    )
    (net (code "146") (name "unconnected-(D52-A-Pad1)") (class "Default")
      (node (ref "D52") (pin "1") (pinfunction "A_1") (pintype "passive"))
    )
    (net (code "147") (name "unconnected-(D52-K-Pad2)") (class "Default")
      (node (ref "D52") (pin "2") (pinfunction "K_2") (pintype "passive"))
    )
    (net (code "148") (name "unconnected-(D53-A-Pad1)") (class "Default")
      (node (ref "D53") (pin "1") (pinfunction "A_1") (pintype "passive"))
    )
    (net (code "149") (name "unconnected-(D53-K-Pad2)") (class "Default")
      (node (ref "D53") (pin "2") (pinfunction "K_2") (pintype "passive"))
    )
    (net (code "150") (name "unconnected-(D54-A-Pad1)") (class "Default")
      (node (ref "D54") (pin "1") (pinfunction "A_1") (pintype "passive"))
    )
    (net (code "151") (name "unconnected-(D54-K-Pad2)") (class "Default")
      (node (ref "D54") (pin "2") (pinfunction "K_2") (pintype "passive"))
    )
    (net (code "152") (name "unconnected-(D55-A-Pad1)") (class "Default")
      (node (ref "D55") (pin "1") (pinfunction "A_1") (pintype "passive"))
    )
    (net (code "153") (name "unconnected-(D55-K-Pad2)") (class "Default")
      (node (ref "D55") (pin "2") (pinfunction "K_2") (pintype "passive"))
    )
    (net (code "154") (name "unconnected-(D56-A-Pad1)") (class "Default")
      (node (ref "D56") (pin "1") (pinfunction "A_1") (pintype "passive"))
    )
    (net (code "155") (name "unconnected-(D56-K-Pad2)") (class "Default")
      (node (ref "D56") (pin "2") (pinfunction "K_2") (pintype "passive"))
    )
    (net (code "156") (name "unconnected-(D57-A-Pad1)") (class "Default")
      (node (ref "D57") (pin "1") (pinfunction "A_1") (pintype "passive"))
    )
    (net (code "157") (name "unconnected-(D57-K-Pad2)") (class "Default")
      (node (ref "D57") (pin "2") (pinfunction "K_2") (pintype "passive"))
    )
    (net (code "158") (name "unconnected-(D58-A-Pad1)") (class "Default")
      (node (ref "D58") (pin "1") (pinfunction "A_1") (pintype "passive"))
    )
    (net (code "159") (name "unconnected-(D58-K-Pad2)") (class "Default")
      (node (ref "D58") (pin "2") (pinfunction "K_2") (pintype "passive"))
    )
    (net (code "160") (name "unconnected-(D59-A-Pad1)") (class "Default")
      (node (ref "D59") (pin "1") (pinfunction "A_1") (pintype "passive"))
    )
    (net (code "161") (name "unconnected-(D59-K-Pad2)") (class "Default")
      (node (ref "D59") (pin "2") (pinfunction "K_2") (pintype "passive"))
    )
    (net (code "162") (name "unconnected-(D60-A-Pad1)") (class "Default")
      (node (ref "D60") (pin "1") (pinfunction "A_1") (pintype "passive"))
    )
    (net (code "163") (name "unconnected-(D60-K-Pad2)") (class "Default")
      (node (ref "D60") (pin "2") (pinfunction "K_2") (pintype "passive"))
    )
    (net (code "164") (name "unconnected-(D61-A-Pad1)") (class "Default")
      (node (ref "D61") (pin "1") (pinfunction "A_1") (pintype "passive"))
    )
    (net (code "165") (name "unconnected-(D61-K-Pad2)") (class "Default")
      (node (ref "D61") (pin "2") (pinfunction "K_2") (pintype "passive"))
    )
    (net (code "166") (name "unconnected-(D62-A-Pad1)") (class "Default")
      (node (ref "D62") (pin "1") (pinfunction "A_1") (pintype "passive"))
    )
    (net (code "167") (name "unconnected-(D62-K-Pad2)") (class "Default")
      (node (ref "D62") (pin "2") (pinfunction "K_2") (pintype "passive"))
    )
    (net (code "168") (name "unconnected-(D63-A-Pad1)") (class "Default")
      (node (ref "D63") (pin "1") (pinfunction "A_1") (pintype "passive"))
    )
    (net (code "169") (name "unconnected-(D63-K-Pad2)") (class "Default")
      (node (ref "D63") (pin "2") (pinfunction "K_2") (pintype "passive"))
    )
    (net (code "170") (name "unconnected-(D64-A-Pad1)") (class "Default")
      (node (ref "D64") (pin "1") (pinfunction "A_1") (pintype "passive"))
    )
    (net (code "171") (name "unconnected-(D64-K-Pad2)") (class "Default")
      (node (ref "D64") (pin "2") (pinfunction "K_2") (pintype "passive"))
    )
    (net (code "172") (name "unconnected-(D65-A-Pad1)") (class "Default")
      (node (ref "D65") (pin "1") (pinfunction "A_1") (pintype "passive"))
    )
    (net (code "173") (name "unconnected-(D65-K-Pad2)") (class "Default")
      (node (ref "D65") (pin "2") (pinfunction "K_2") (pintype "passive"))
    )
    (net (code "174") (name "unconnected-(D66-A-Pad1)") (class "Default")
      (node (ref "D66") (pin "1") (pinfunction "A_1") (pintype "passive"))
    )
    (net (code "175") (name "unconnected-(D66-K-Pad2)") (class "Default")
      (node (ref "D66") (pin "2") (pinfunction "K_2") (pintype "passive"))
    )
    (net (code "176") (name "unconnected-(D67-A-Pad1)") (class "Default")
      (node (ref "D67") (pin "1") (pinfunction "A_1") (pintype "passive"))
    )
    (net (code "177") (name "unconnected-(D67-K-Pad2)") (class "Default")
      (node (ref "D67") (pin "2") (pinfunction "K_2") (pintype "passive"))
    )
    (net (code "178") (name "unconnected-(D68-A-Pad1)") (class "Default")
      (node (ref "D68") (pin "1") (pinfunction "A_1") (pintype "passive"))
    )
    (net (code "179") (name "unconnected-(D68-K-Pad2)") (class "Default")
      (node (ref "D68") (pin "2") (pinfunction "K_2") (pintype "passive"))
    )
    (net (code "180") (name "unconnected-(D69-A-Pad1)") (class "Default")
      (node (ref "D69") (pin "1") (pinfunction "A_1") (pintype "passive"))
    )
    (net (code "181") (name "unconnected-(D69-K-Pad2)") (class "Default")
      (node (ref "D69") (pin "2") (pinfunction "K_2") (pintype "passive"))
    )
    (net (code "182") (name "unconnected-(D70-A-Pad1)") (class "Default")
      (node (ref "D70") (pin "1") (pinfunction "A_1") (pintype "passive"))
    )
    (net (code "183") (name "unconnected-(D70-K-Pad2)") (class "Default")
      (node (ref "D70") (pin "2") (pinfunction "K_2") (pintype "passive"))
    )
    (net (code "184") (name "unconnected-(D71-A-Pad1)") (class "Default")
      (node (ref "D71") (pin "1") (pinfunction "A_1") (pintype "passive"))
    )
    (net (code "185") (name "unconnected-(D71-K-Pad2)") (class "Default")
      (node (ref "D71") (pin "2") (pinfunction "K_2") (pintype "passive"))
    )
    (net (code "186") (name "unconnected-(D72-A-Pad1)") (class "Default")
      (node (ref "D72") (pin "1") (pinfunction "A_1") (pintype "passive"))
    )
    (net (code "187") (name "unconnected-(D72-K-Pad2)") (class "Default")
      (node (ref "D72") (pin "2") (pinfunction "K_2") (pintype "passive"))
    )
    (net (code "188") (name "unconnected-(D73-A-Pad1)") (class "Default")
      (node (ref "D73") (pin "1") (pinfunction "A_1") (pintype "passive"))
    )
    (net (code "189") (name "unconnected-(D73-K-Pad2)") (class "Default")
      (node (ref "D73") (pin "2") (pinfunction "K_2") (pintype "passive"))
    )
    (net (code "190") (name "unconnected-(D74-A-Pad1)") (class "Default")
      (node (ref "D74") (pin "1") (pinfunction "A_1") (pintype "passive"))
    )
    (net (code "191") (name "unconnected-(D74-K-Pad2)") (class "Default")
      (node (ref "D74") (pin "2") (pinfunction "K_2") (pintype "passive"))
    )
    (net (code "192") (name "unconnected-(D75-A-Pad1)") (class "Default")
      (node (ref "D75") (pin "1") (pinfunction "A_1") (pintype "passive"))
    )
    (net (code "193") (name "unconnected-(D75-K-Pad2)") (class "Default")
      (node (ref "D75") (pin "2") (pinfunction "K_2") (pintype "passive"))
    )
    (net (code "194") (name "unconnected-(D76-A-Pad1)") (class "Default")
      (node (ref "D76") (pin "1") (pinfunction "A_1") (pintype "passive"))
    )
    (net (code "195") (name "unconnected-(D76-K-Pad2)") (class "Default")
      (node (ref "D76") (pin "2") (pinfunction "K_2") (pintype "passive"))
    )
    (net (code "196") (name "unconnected-(D77-A-Pad1)") (class "Default")
      (node (ref "D77") (pin "1") (pinfunction "A_1") (pintype "passive"))
    )
    (net (code "197") (name "unconnected-(D77-K-Pad2)") (class "Default")
      (node (ref "D77") (pin "2") (pinfunction "K_2") (pintype "passive"))
    )
    (net (code "198") (name "unconnected-(D78-A-Pad1)") (class "Default")
      (node (ref "D78") (pin "1") (pinfunction "A_1") (pintype "passive"))
    )
    (net (code "199") (name "unconnected-(D78-K-Pad2)") (class "Default")
      (node (ref "D78") (pin "2") (pinfunction "K_2") (pintype "passive"))
    )
    (net (code "200") (name "unconnected-(D79-A-Pad1)") (class "Default")
      (node (ref "D79") (pin "1") (pinfunction "A_1") (pintype "passive"))
    )
    (net (code "201") (name "unconnected-(D79-K-Pad2)") (class "Default")
      (node (ref "D79") (pin "2") (pinfunction "K_2") (pintype "passive"))
    )
    (net (code "202") (name "unconnected-(D80-A-Pad1)") (class "Default")
      (node (ref "D80") (pin "1") (pinfunction "A_1") (pintype "passive"))
    )
    (net (code "203") (name "unconnected-(D80-K-Pad2)") (class "Default")
      (node (ref "D80") (pin "2") (pinfunction "K_2") (pintype "passive"))
    )
    (net (code "204") (name "unconnected-(D81-A-Pad1)") (class "Default")
      (node (ref "D81") (pin "1") (pinfunction "A_1") (pintype "passive"))
    )
    (net (code "205") (name "unconnected-(D81-K-Pad2)") (class "Default")
      (node (ref "D81") (pin "2") (pinfunction "K_2") (pintype "passive"))
    )
    (net (code "206") (name "unconnected-(D82-A-Pad1)") (class "Default")
      (node (ref "D82") (pin "1") (pinfunction "A_1") (pintype "passive"))
    )
    (net (code "207") (name "unconnected-(D82-K-Pad2)") (class "Default")
      (node (ref "D82") (pin "2") (pinfunction "K_2") (pintype "passive"))
    )
    (net (code "208") (name "unconnected-(D83-A-Pad1)") (class "Default")
      (node (ref "D83") (pin "1") (pinfunction "A_1") (pintype "passive"))
    )
    (net (code "209") (name "unconnected-(D83-K-Pad2)") (class "Default")
      (node (ref "D83") (pin "2") (pinfunction "K_2") (pintype "passive"))
    )
    (net (code "210") (name "unconnected-(D84-A-Pad1)") (class "Default")
      (node (ref "D84") (pin "1") (pinfunction "A_1") (pintype "passive"))
    )
    (net (code "211") (name "unconnected-(D84-K-Pad2)") (class "Default")
      (node (ref "D84") (pin "2") (pinfunction "K_2") (pintype "passive"))
    )
    (net (code "212") (name "unconnected-(D85-A-Pad1)") (class "Default")
      (node (ref "D85") (pin "1") (pinfunction "A_1") (pintype "passive"))
    )
    (net (code "213") (name "unconnected-(D85-K-Pad2)") (class "Default")
      (node (ref "D85") (pin "2") (pinfunction "K_2") (pintype "passive"))
    )
    (net (code "214") (name "unconnected-(D86-A-Pad1)") (class "Default")
      (node (ref "D86") (pin "1") (pinfunction "A_1") (pintype "passive"))
    )
    (net (code "215") (name "unconnected-(D86-K-Pad2)") (class "Default")
      (node (ref "D86") (pin "2") (pinfunction "K_2") (pintype "passive"))
    )
    (net (code "216") (name "unconnected-(D87-A-Pad1)") (class "Default")
      (node (ref "D87") (pin "1") (pinfunction "A_1") (pintype "passive"))
    )
    (net (code "217") (name "unconnected-(D87-K-Pad2)") (class "Default")
      (node (ref "D87") (pin "2") (pinfunction "K_2") (pintype "passive"))
    )
    (net (code "218") (name "unconnected-(D88-A-Pad1)") (class "Default")
      (node (ref "D88") (pin "1") (pinfunction "A_1") (pintype "passive"))
    )
    (net (code "219") (name "unconnected-(D88-K-Pad2)") (class "Default")
      (node (ref "D88") (pin "2") (pinfunction "K_2") (pintype "passive"))
    )
    (net (code "220") (name "unconnected-(D89-A-Pad1)") (class "Default")
      (node (ref "D89") (pin "1") (pinfunction "A_1") (pintype "passive"))
    )
    (net (code "221") (name "unconnected-(D89-K-Pad2)") (class "Default")
      (node (ref "D89") (pin "2") (pinfunction "K_2") (pintype "passive"))
    )
    (net (code "222") (name "unconnected-(D90-A-Pad1)") (class "Default")
      (node (ref "D90") (pin "1") (pinfunction "A_1") (pintype "passive"))
    )
    (net (code "223") (name "unconnected-(D90-K-Pad2)") (class "Default")
      (node (ref "D90") (pin "2") (pinfunction "K_2") (pintype "passive"))
    )
    (net (code "224") (name "unconnected-(D91-A-Pad1)") (class "Default")
      (node (ref "D91") (pin "1") (pinfunction "A_1") (pintype "passive"))
    )
    (net (code "225") (name "unconnected-(D91-K-Pad2)") (class "Default")
      (node (ref "D91") (pin "2") (pinfunction "K_2") (pintype "passive"))
    )
    (net (code "226") (name "unconnected-(D92-A-Pad1)") (class "Default")
      (node (ref "D92") (pin "1") (pinfunction "A_1") (pintype "passive"))
    )
    (net (code "227") (name "unconnected-(D92-K-Pad2)") (class "Default")
      (node (ref "D92") (pin "2") (pinfunction "K_2") (pintype "passive"))
    )
    (net (code "228") (name "unconnected-(D93-A-Pad1)") (class "Default")
      (node (ref "D93") (pin "1") (pinfunction "A_1") (pintype "passive"))
    )
    (net (code "229") (name "unconnected-(D93-K-Pad2)") (class "Default")
      (node (ref "D93") (pin "2") (pinfunction "K_2") (pintype "passive"))
    )
    (net (code "230") (name "unconnected-(D94-A-Pad1)") (class "Default")
      (node (ref "D94") (pin "1") (pinfunction "A_1") (pintype "passive"))
    )
    (net (code "231") (name "unconnected-(D94-K-Pad2)") (class "Default")
      (node (ref "D94") (pin "2") (pinfunction "K_2") (pintype "passive"))
    )
    (net (code "232") (name "unconnected-(D95-A-Pad1)") (class "Default")
      (node (ref "D95") (pin "1") (pinfunction "A_1") (pintype "passive"))
    )
    (net (code "233") (name "unconnected-(D95-K-Pad2)") (class "Default")
      (node (ref "D95") (pin "2") (pinfunction "K_2") (pintype "passive"))
    )
    (net (code "234") (name "unconnected-(D96-A-Pad1)") (class "Default")
      (node (ref "D96") (pin "1") (pinfunction "A_1") (pintype "passive"))
    )
    (net (code "235") (name "unconnected-(D96-K-Pad2)") (class "Default")
      (node (ref "D96") (pin "2") (pinfunction "K_2") (pintype "passive"))
    )
    (net (code "236") (name "unconnected-(D97-A-Pad1)") (class "Default")
      (node (ref "D97") (pin "1") (pinfunction "A_1") (pintype "passive"))
    )
    (net (code "237") (name "unconnected-(D97-K-Pad2)") (class "Default")
      (node (ref "D97") (pin "2") (pinfunction "K_2") (pintype "passive"))
    )
    (net (code "238") (name "unconnected-(D98-A-Pad1)") (class "Default")
      (node (ref "D98") (pin "1") (pinfunction "A_1") (pintype "passive"))
    )
    (net (code "239") (name "unconnected-(D98-K-Pad2)") (class "Default")
      (node (ref "D98") (pin "2") (pinfunction "K_2") (pintype "passive"))
    )
    (net (code "240") (name "unconnected-(D99-A-Pad1)") (class "Default")
      (node (ref "D99") (pin "1") (pinfunction "A_1") (pintype "passive"))
    )
    (net (code "241") (name "unconnected-(D99-K-Pad2)") (class "Default")
      (node (ref "D99") (pin "2") (pinfunction "K_2") (pintype "passive"))
    )
    (net (code "242") (name "unconnected-(D100-A-Pad1)") (class "Default")
      (node (ref "D100") (pin "1") (pinfunction "A_1") (pintype "passive"))
    )
    (net (code "243") (name "unconnected-(D100-K-Pad2)") (class "Default")
      (node (ref "D100") (pin "2") (pinfunction "K_2") (pintype "passive"))
    )
    (net (code "244") (name "unconnected-(D101-A-Pad1)") (class "Default")
      (node (ref "D101") (pin "1") (pinfunction "A_1") (pintype "passive"))
    )
    (net (code "245") (name "unconnected-(D101-K-Pad2)") (class "Default")
      (node (ref "D101") (pin "2") (pinfunction "K_2") (pintype "passive"))
    )
    (net (code "246") (name "unconnected-(D102-A-Pad1)") (class "Default")
      (node (ref "D102") (pin "1") (pinfunction "A_1") (pintype "passive"))
    )
    (net (code "247") (name "unconnected-(D102-K-Pad2)") (class "Default")
      (node (ref "D102") (pin "2") (pinfunction "K_2") (pintype "passive"))
    )
    (net (code "248") (name "unconnected-(D103-A-Pad1)") (class "Default")
      (node (ref "D103") (pin "1") (pinfunction "A_1") (pintype "passive"))
    )
    (net (code "249") (name "unconnected-(D103-K-Pad2)") (class "Default")
      (node (ref "D103") (pin "2") (pinfunction "K_2") (pintype "passive"))
    )
    (net (code "250") (name "unconnected-(D104-A-Pad1)") (class "Default")
      (node (ref "D104") (pin "1") (pinfunction "A_1") (pintype "passive"))
    )
    (net (code "251") (name "unconnected-(D104-K-Pad2)") (class "Default")
      (node (ref "D104") (pin "2") (pinfunction "K_2") (pintype "passive"))
    )
    (net (code "252") (name "unconnected-(D105-A-Pad1)") (class "Default")
      (node (ref "D105") (pin "1") (pinfunction "A_1") (pintype "passive"))
    )
    (net (code "253") (name "unconnected-(D105-K-Pad2)") (class "Default")
      (node (ref "D105") (pin "2") (pinfunction "K_2") (pintype "passive"))
    )
    (net (code "254") (name "unconnected-(D106-A-Pad1)") (class "Default")
      (node (ref "D106") (pin "1") (pinfunction "A_1") (pintype "passive"))
    )
    (net (code "255") (name "unconnected-(D106-K-Pad2)") (class "Default")
      (node (ref "D106") (pin "2") (pinfunction "K_2") (pintype "passive"))
    )
    (net (code "256") (name "unconnected-(D107-A-Pad1)") (class "Default")
      (node (ref "D107") (pin "1") (pinfunction "A_1") (pintype "passive"))
    )
    (net (code "257") (name "unconnected-(D107-K-Pad2)") (class "Default")
      (node (ref "D107") (pin "2") (pinfunction "K_2") (pintype "passive"))
    )
    (net (code "258") (name "unconnected-(D108-A-Pad1)") (class "Default")
      (node (ref "D108") (pin "1") (pinfunction "A_1") (pintype "passive"))
    )
    (net (code "259") (name "unconnected-(D108-K-Pad2)") (class "Default")
      (node (ref "D108") (pin "2") (pinfunction "K_2") (pintype "passive"))
    )
    (net (code "260") (name "unconnected-(D109-A-Pad1)") (class "Default")
      (node (ref "D109") (pin "1") (pinfunction "A_1") (pintype "passive"))
    )
    (net (code "261") (name "unconnected-(D109-K-Pad2)") (class "Default")
      (node (ref "D109") (pin "2") (pinfunction "K_2") (pintype "passive"))
    )
    (net (code "262") (name "unconnected-(D110-A-Pad1)") (class "Default")
      (node (ref "D110") (pin "1") (pinfunction "A_1") (pintype "passive"))
    )
    (net (code "263") (name "unconnected-(D110-K-Pad2)") (class "Default")
      (node (ref "D110") (pin "2") (pinfunction "K_2") (pintype "passive"))
    )
    (net (code "264") (name "unconnected-(D111-A-Pad1)") (class "Default")
      (node (ref "D111") (pin "1") (pinfunction "A_1") (pintype "passive"))
    )
    (net (code "265") (name "unconnected-(D111-K-Pad2)") (class "Default")
      (node (ref "D111") (pin "2") (pinfunction "K_2") (pintype "passive"))
    )
    (net (code "266") (name "unconnected-(D112-A-Pad1)") (class "Default")
      (node (ref "D112") (pin "1") (pinfunction "A_1") (pintype "passive"))
    )
    (net (code "267") (name "unconnected-(D112-K-Pad2)") (class "Default")
      (node (ref "D112") (pin "2") (pinfunction "K_2") (pintype "passive"))
    )
    (net (code "268") (name "unconnected-(D113-A-Pad1)") (class "Default")
      (node (ref "D113") (pin "1") (pinfunction "A_1") (pintype "passive"))
    )
    (net (code "269") (name "unconnected-(D113-K-Pad2)") (class "Default")
      (node (ref "D113") (pin "2") (pinfunction "K_2") (pintype "passive"))
    )
    (net (code "270") (name "unconnected-(D114-A-Pad1)") (class "Default")
      (node (ref "D114") (pin "1") (pinfunction "A_1") (pintype "passive"))
    )
    (net (code "271") (name "unconnected-(D114-K-Pad2)") (class "Default")
      (node (ref "D114") (pin "2") (pinfunction "K_2") (pintype "passive"))
    )
    (net (code "272") (name "unconnected-(D115-A-Pad1)") (class "Default")
      (node (ref "D115") (pin "1") (pinfunction "A_1") (pintype "passive"))
    )
    (net (code "273") (name "unconnected-(D115-K-Pad2)") (class "Default")
      (node (ref "D115") (pin "2") (pinfunction "K_2") (pintype "passive"))
    )
    (net (code "274") (name "unconnected-(D116-A-Pad1)") (class "Default")
      (node (ref "D116") (pin "1") (pinfunction "A_1") (pintype "passive"))
    )
    (net (code "275") (name "unconnected-(D116-K-Pad2)") (class "Default")
      (node (ref "D116") (pin "2") (pinfunction "K_2") (pintype "passive"))
    )
    (net (code "276") (name "unconnected-(D117-A-Pad1)") (class "Default")
      (node (ref "D117") (pin "1") (pinfunction "A_1") (pintype "passive"))
    )
    (net (code "277") (name "unconnected-(D117-K-Pad2)") (class "Default")
      (node (ref "D117") (pin "2") (pinfunction "K_2") (pintype "passive"))
    )
    (net (code "278") (name "unconnected-(D118-A-Pad1)") (class "Default")
      (node (ref "D118") (pin "1") (pinfunction "A_1") (pintype "passive"))
    )
    (net (code "279") (name "unconnected-(D118-K-Pad2)") (class "Default")
      (node (ref "D118") (pin "2") (pinfunction "K_2") (pintype "passive"))
    )
    (net (code "280") (name "unconnected-(D119-A-Pad1)") (class "Default")
      (node (ref "D119") (pin "1") (pinfunction "A_1") (pintype "passive"))
    )
    (net (code "281") (name "unconnected-(D119-K-Pad2)") (class "Default")
      (node (ref "D119") (pin "2") (pinfunction "K_2") (pintype "passive"))
    )
    (net (code "282") (name "unconnected-(D120-A-Pad1)") (class "Default")
      (node (ref "D120") (pin "1") (pinfunction "A_1") (pintype "passive"))
    )
    (net (code "283") (name "unconnected-(D120-K-Pad2)") (class "Default")
      (node (ref "D120") (pin "2") (pinfunction "K_2") (pintype "passive"))
    )
    (net (code "284") (name "unconnected-(D121-A-Pad1)") (class "Default")
      (node (ref "D121") (pin "1") (pinfunction "A_1") (pintype "passive"))
    )
    (net (code "285") (name "unconnected-(D121-K-Pad2)") (class "Default")
      (node (ref "D121") (pin "2") (pinfunction "K_2") (pintype "passive"))
    )
    (net (code "286") (name "unconnected-(D122-A-Pad1)") (class "Default")
      (node (ref "D122") (pin "1") (pinfunction "A_1") (pintype "passive"))
    )
    (net (code "287") (name "unconnected-(D122-K-Pad2)") (class "Default")
      (node (ref "D122") (pin "2") (pinfunction "K_2") (pintype "passive"))
    )
    (net (code "288") (name "unconnected-(D123-A-Pad1)") (class "Default")
      (node (ref "D123") (pin "1") (pinfunction "A_1") (pintype "passive"))
    )
    (net (code "289") (name "unconnected-(D123-K-Pad2)") (class "Default")
      (node (ref "D123") (pin "2") (pinfunction "K_2") (pintype "passive"))
    )
    (net (code "290") (name "unconnected-(D124-A-Pad1)") (class "Default")
      (node (ref "D124") (pin "1") (pinfunction "A_1") (pintype "passive"))
    )
    (net (code "291") (name "unconnected-(D124-K-Pad2)") (class "Default")
      (node (ref "D124") (pin "2") (pinfunction "K_2") (pintype "passive"))
    )
    (net (code "292") (name "unconnected-(D125-A-Pad1)") (class "Default")
      (node (ref "D125") (pin "1") (pinfunction "A_1") (pintype "passive"))
    )
    (net (code "293") (name "unconnected-(D125-K-Pad2)") (class "Default")
      (node (ref "D125") (pin "2") (pinfunction "K_2") (pintype "passive"))
    )
    (net (code "294") (name "unconnected-(D126-A-Pad1)") (class "Default")
      (node (ref "D126") (pin "1") (pinfunction "A_1") (pintype "passive"))
    )
    (net (code "295") (name "unconnected-(D126-K-Pad2)") (class "Default")
      (node (ref "D126") (pin "2") (pinfunction "K_2") (pintype "passive"))
    )
    (net (code "296") (name "unconnected-(D127-A-Pad1)") (class "Default")
      (node (ref "D127") (pin "1") (pinfunction "A_1") (pintype "passive"))
    )
    (net (code "297") (name "unconnected-(D127-K-Pad2)") (class "Default")
      (node (ref "D127") (pin "2") (pinfunction "K_2") (pintype "passive"))
    )
    (net (code "298") (name "unconnected-(D128-A-Pad1)") (class "Default")
      (node (ref "D128") (pin "1") (pinfunction "A_1") (pintype "passive"))
    )
    (net (code "299") (name "unconnected-(D128-K-Pad2)") (class "Default")
      (node (ref "D128") (pin "2") (pinfunction "K_2") (pintype "passive"))
    )
  )
)
